# IO.net
KiCad netlist of a schematic drawn in Altium Designer
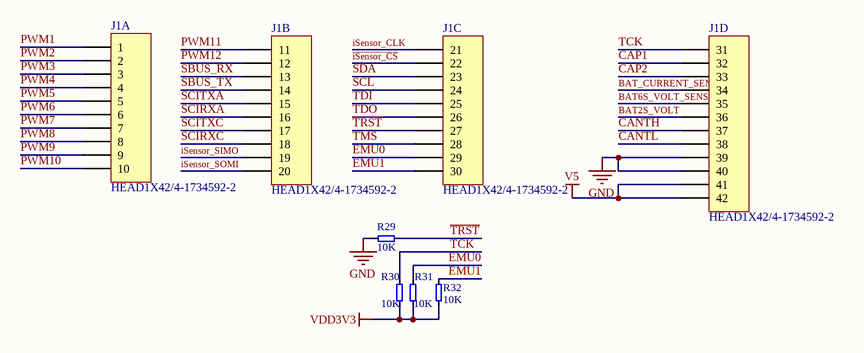
[diagram p0: IO.SchDoc]

(export (version "E")
  (design (tool "Eeschema 10.0.6"))
  (components
    (comp (ref "J1")
      (value "HEAD1X42/4-1734592-2")
      (footprint "FPC0.5-42")
      (libsource (lib "研发中心原理图库文件") (part "HEAD1X42"))
    )
    (comp (ref "R29") (value "10K") (footprint "0603R") (libsource (lib "研发中心原理图库文件") (part "R")))
    (comp (ref "R30") (value "10K") (footprint "0603R") (libsource (lib "研发中心原理图库文件") (part "R")))
    (comp (ref "R31") (value "10K") (footprint "0603R") (libsource (lib "研发中心原理图库文件") (part "R")))
    (comp (ref "R32") (value "10K") (footprint "0603R") (libsource (lib "研发中心原理图库文件") (part "R")))
  )
  (nets
    (net (code "1") (name "/BAT2S_VOLT") (class "Default")
      (node (ref "J1") (pin "36") (pinfunction "36_36") (pintype "passive"))
    )
    (net (code "2") (name "/BAT6S_VOLT_SENSE") (class "Default")
      (node (ref "J1") (pin "35") (pinfunction "35_35") (pintype "passive"))
    )
    (net (code "3") (name "/BAT_CURRENT_SENSE") (class "Default")
      (node (ref "J1") (pin "34") (pinfunction "34_34") (pintype "passive"))
    )
    (net (code "4") (name "/CANTH") (class "Default")
      (node (ref "J1") (pin "37") (pinfunction "37_37") (pintype "passive"))
    )
    (net (code "5") (name "/CANTL") (class "Default")
      (node (ref "J1") (pin "38") (pinfunction "38_38") (pintype "passive"))
    )
    (net (code "6") (name "/CAP1") (class "Default")
      (node (ref "J1") (pin "32") (pinfunction "32_32") (pintype "passive"))
    )
    (net (code "7") (name "/CAP2") (class "Default")
      (node (ref "J1") (pin "33") (pinfunction "33_33") (pintype "passive"))
    )
    (net (code "8") (name "/EMU0") (class "Default")
      (node (ref "J1") (pin "29") (pinfunction "29_29") (pintype "passive"))
      (node (ref "R31") (pin "2") (pintype "passive"))
    )
    (net (code "9") (name "/EMU1") (class "Default")
      (node (ref "J1") (pin "30") (pinfunction "30_30") (pintype "passive"))
      (node (ref "R32") (pin "2") (pintype "passive"))
    )
    (net (code "10") (name "/PWM1") (class "Default")
      (node (ref "J1") (pin "1") (pinfunction "1_1") (pintype "passive"))
    )
    (net (code "11") (name "/PWM2") (class "Default")
      (node (ref "J1") (pin "2") (pinfunction "2_2") (pintype "passive"))
    )
    (net (code "12") (name "/PWM3") (class "Default")
      (node (ref "J1") (pin "3") (pinfunction "3_3") (pintype "passive"))
    )
    (net (code "13") (name "/PWM4") (class "Default")
      (node (ref "J1") (pin "4") (pinfunction "4_4") (pintype "passive"))
    )
    (net (code "14") (name "/PWM5") (class "Default")
      (node (ref "J1") (pin "5") (pinfunction "5_5") (pintype "passive"))
    )
    (net (code "15") (name "/PWM6") (class "Default")
      (node (ref "J1") (pin "6") (pinfunction "6_6") (pintype "passive"))
    )
    (net (code "16") (name "/PWM7") (class "Default")
      (node (ref "J1") (pin "7") (pinfunction "7_7") (pintype "passive"))
    )
    (net (code "17") (name "/PWM8") (class "Default")
      (node (ref "J1") (pin "8") (pinfunction "8_8") (pintype "passive"))
    )
    (net (code "18") (name "/PWM9") (class "Default")
      (node (ref "J1") (pin "9") (pinfunction "9_9") (pintype "passive"))
    )
    (net (code "19") (name "/PWM10") (class "Default")
      (node (ref "J1") (pin "10") (pinfunction "10_10") (pintype "passive"))
    )
    (net (code "20") (name "/PWM11") (class "Default")
      (node (ref "J1") (pin "11") (pinfunction "11_11") (pintype "passive"))
    )
    (net (code "21") (name "/PWM12") (class "Default")
      (node (ref "J1") (pin "12") (pinfunction "12_12") (pintype "passive"))
    )
    (net (code "22") (name "/SBUS_RX") (class "Default")
      (node (ref "J1") (pin "13") (pinfunction "13_13") (pintype "passive"))
    )
    (net (code "23") (name "/SBUS_TX") (class "Default")
      (node (ref "J1") (pin "14") (pinfunction "14_14") (pintype "passive"))
    )
    (net (code "24") (name "/SCIRXA") (class "Default")
      (node (ref "J1") (pin "16") (pinfunction "16_16") (pintype "passive"))
    )
    (net (code "25") (name "/SCIRXC") (class "Default")
      (node (ref "J1") (pin "18") (pinfunction "18_18") (pintype "passive"))
    )
    (net (code "26") (name "/SCITXA") (class "Default")
      (node (ref "J1") (pin "15") (pinfunction "15_15") (pintype "passive"))
    )
    (net (code "27") (name "/SCITXC") (class "Default")
      (node (ref "J1") (pin "17") (pinfunction "17_17") (pintype "passive"))
    )
    (net (code "28") (name "/SCL") (class "Default")
      (node (ref "J1") (pin "24") (pinfunction "24_24") (pintype "passive"))
    )
    (net (code "29") (name "/SDA") (class "Default")
      (node (ref "J1") (pin "23") (pinfunction "23_23") (pintype "passive"))
    )
    (net (code "30") (name "/TCK") (class "Default")
      (node (ref "J1") (pin "31") (pinfunction "31_31") (pintype "passive"))
      (node (ref "R30") (pin "2") (pintype "passive"))
    )
    (net (code "31") (name "/TDI") (class "Default")
      (node (ref "J1") (pin "25") (pinfunction "25_25") (pintype "passive"))
    )
    (net (code "32") (name "/TDO") (class "Default")
      (node (ref "J1") (pin "26") (pinfunction "26_26") (pintype "passive"))
    )
    (net (code "33") (name "/TMS") (class "Default")
      (node (ref "J1") (pin "28") (pinfunction "28_28") (pintype "passive"))
    )
    (net (code "34") (name "/iSensor_CLK") (class "Default")
      (node (ref "J1") (pin "21") (pinfunction "21_21") (pintype "passive"))
    )
    (net (code "35") (name "/iSensor_SIMO") (class "Default")
      (node (ref "J1") (pin "19") (pinfunction "19_19") (pintype "passive"))
    )
    (net (code "36") (name "/iSensor_SOMI") (class "Default")
      (node (ref "J1") (pin "20") (pinfunction "20_20") (pintype "passive"))
    )
    (net (code "37") (name "/~{TRST}") (class "Default")
      (node (ref "J1") (pin "27") (pinfunction "27_27") (pintype "passive"))
      (node (ref "R29") (pin "2") (pintype "passive"))
    )
    (net (code "38") (name "/~{iSensor_CS}") (class "Default")
      (node (ref "J1") (pin "22") (pinfunction "22_22") (pintype "passive"))
    )
    (net (code "39") (name "GND") (class "Default")
      (node (ref "J1") (pin "39") (pinfunction "39_39") (pintype "passive"))
      (node (ref "J1") (pin "40") (pinfunction "40_40") (pintype "passive"))
      (node (ref "R29") (pin "1") (pintype "passive"))
    )
    (net (code "40") (name "V5") (class "Default")
      (node (ref "J1") (pin "40") (pinfunction "41_40") (pintype "passive"))
    )
    (net (code "41") (name "VDD3V3") (class "Default")
      (node (ref "R30") (pin "1") (pintype "passive"))
      (node (ref "R31") (pin "1") (pintype "passive"))
      (node (ref "R32") (pin "1") (pintype "passive"))
    )
  )
)
